# ATtiny_45_and_85_programmer_shield_withI.net
KiCad netlist of a schematic drawn in EAGLE
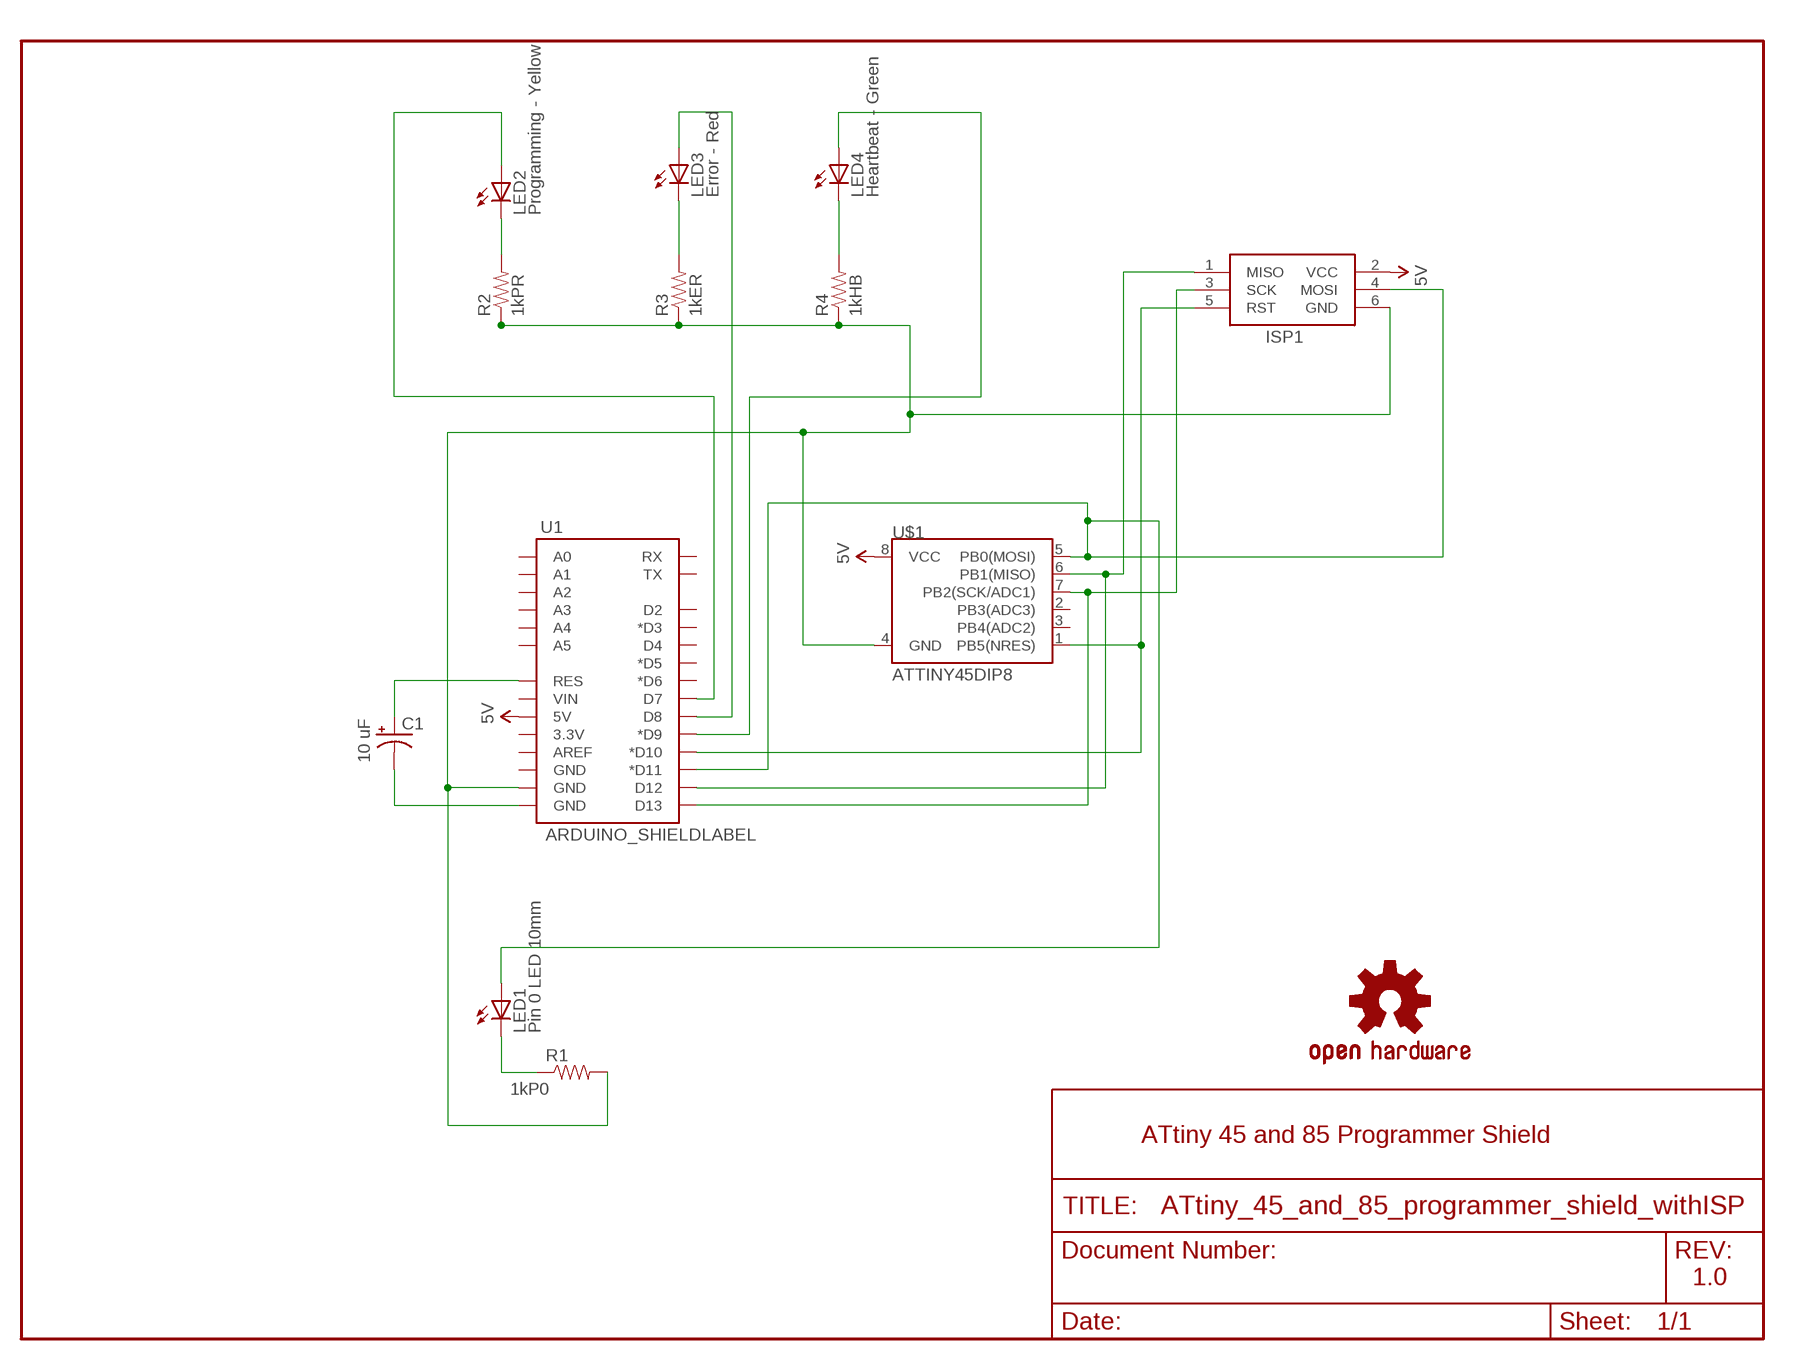
[diagram p0: schematic, sheet 1]

(export (version "E")
  (design (tool "Eeschema 10.0.6"))
  (components
    (comp (ref "C1")
      (value "10 uF")
      (footprint "eagle-import:CPOL-RADIAL-10UF-25V")
      (libsource (lib "eagle-import") (part "CAP_POLPTH2"))
    )
    (comp (ref "ISP1")
      (value "AVRISP-6")
      (footprint "eagle-import:AVRISP")
      (libsource (lib "eagle-import") (part "AVRISP-6"))
    )
    (comp (ref "LED1")
      (value "Pin 0 LED 10mm")
      (footprint "eagle-import:LED10MM")
      (libsource (lib "eagle-import") (part "LED10MM"))
    )
    (comp (ref "LED2")
      (value "Programming - Yellow")
      (footprint "eagle-import:LED5MM")
      (libsource (lib "eagle-import") (part "LED5MM"))
    )
    (comp (ref "LED3")
      (value "Error - Red")
      (footprint "eagle-import:LED5MM")
      (libsource (lib "eagle-import") (part "LED5MM"))
    )
    (comp (ref "LED4")
      (value "Heartbeat - Green")
      (footprint "eagle-import:LED5MM")
      (libsource (lib "eagle-import") (part "LED5MM"))
    )
    (comp (ref "R1")
      (value "1kP0")
      (footprint "eagle-import:1_6W-RES")
      (libsource (lib "eagle-import") (part "RESISTORPTH-1/6W"))
    )
    (comp (ref "R2")
      (value "1kPR")
      (footprint "eagle-import:1_6W-RES")
      (libsource (lib "eagle-import") (part "RESISTORPTH-1/6W"))
    )
    (comp (ref "R3")
      (value "1kER")
      (footprint "eagle-import:1_6W-RES")
      (libsource (lib "eagle-import") (part "RESISTORPTH-1/6W"))
    )
    (comp (ref "R4")
      (value "1kHB")
      (footprint "eagle-import:1_6W-RES")
      (libsource (lib "eagle-import") (part "RESISTORPTH-1/6W"))
    )
    (comp (ref "U$1")
      (value "ATTINY45DIP8")
      (footprint "eagle-import:DIP08")
      (libsource (lib "eagle-import") (part "ATTINY45DIP8"))
    )
    (comp (ref "U$4")
      (value "OSHW-LOGOL")
      (footprint "eagle-import:OSHW-LOGO-L")
      (libsource (lib "eagle-import") (part "OSHW-LOGOL"))
    )
    (comp (ref "U1")
      (value "ARDUINO_SHIELDLABEL")
      (footprint "eagle-import:DUEMILANOVE_SHIELD")
      (libsource (lib "eagle-import") (part "ARDUINO_SHIELDLABEL"))
    )
  )
  (nets
    (net (code "1") (name "5V") (class "Default")
      (node (ref "ISP1") (pin "2") (pinfunction "VCC_2") (pintype "power_in"))
      (node (ref "U$1") (pin "8") (pinfunction "VCC_8") (pintype "bidirectional"))
      (node (ref "U1") (pin "5V") (pinfunction "5V_5V") (pintype "bidirectional"))
    )
    (net (code "2") (name "Net-(C1-+)") (class "Default")
      (node (ref "C1") (pin "1") (pinfunction "+_1") (pintype "passive"))
      (node (ref "U1") (pin "RES") (pinfunction "RES_RES") (pintype "bidirectional"))
    )
    (net (code "3") (name "Net-(C1--)") (class "Default")
      (node (ref "C1") (pin "2") (pinfunction "-_2") (pintype "passive"))
      (node (ref "U1") (pin "GND@0") (pinfunction "GND_GND@0") (pintype "bidirectional"))
    )
    (net (code "4") (name "Net-(ISP1-GND)") (class "Default")
      (node (ref "ISP1") (pin "6") (pinfunction "GND_6") (pintype "power_in"))
      (node (ref "R1") (pin "2") (pinfunction "2_2") (pintype "passive"))
      (node (ref "R2") (pin "1") (pinfunction "1_1") (pintype "passive"))
      (node (ref "R3") (pin "1") (pinfunction "1_1") (pintype "passive"))
      (node (ref "R4") (pin "1") (pinfunction "1_1") (pintype "passive"))
      (node (ref "U$1") (pin "4") (pinfunction "GND_4") (pintype "bidirectional"))
      (node (ref "U1") (pin "GND@1") (pinfunction "GND_GND@1") (pintype "bidirectional"))
    )
    (net (code "5") (name "Net-(ISP1-MISO)") (class "Default")
      (node (ref "ISP1") (pin "1") (pinfunction "MISO_1") (pintype "input"))
      (node (ref "U$1") (pin "6") (pinfunction "PB1(MISO)_6") (pintype "bidirectional"))
      (node (ref "U1") (pin "D12") (pinfunction "D12_D12") (pintype "bidirectional"))
    )
    (net (code "6") (name "Net-(ISP1-MOSI)") (class "Default")
      (node (ref "ISP1") (pin "4") (pinfunction "MOSI_4") (pintype "output"))
      (node (ref "LED1") (pin "A") (pinfunction "A_A") (pintype "passive"))
      (node (ref "U$1") (pin "5") (pinfunction "PB0(MOSI)_5") (pintype "bidirectional"))
      (node (ref "U1") (pin "D11") (pinfunction "*D11_D11") (pintype "bidirectional"))
    )
    (net (code "7") (name "Net-(ISP1-RST)") (class "Default")
      (node (ref "ISP1") (pin "5") (pinfunction "RST_5") (pintype "output"))
      (node (ref "U$1") (pin "1") (pinfunction "PB5(NRES)_1") (pintype "bidirectional"))
      (node (ref "U1") (pin "D10") (pinfunction "*D10_D10") (pintype "bidirectional"))
    )
    (net (code "8") (name "Net-(ISP1-SCK)") (class "Default")
      (node (ref "ISP1") (pin "3") (pinfunction "SCK_3") (pintype "output"))
      (node (ref "U$1") (pin "7") (pinfunction "PB2(SCK/ADC1)_7") (pintype "bidirectional"))
      (node (ref "U1") (pin "D13") (pinfunction "D13_D13") (pintype "bidirectional"))
    )
    (net (code "9") (name "Net-(LED1-PadC)") (class "Default")
      (node (ref "LED1") (pin "C") (pinfunction "C_C") (pintype "passive"))
      (node (ref "R1") (pin "1") (pinfunction "1_1") (pintype "passive"))
    )
    (net (code "10") (name "Net-(LED2-C)") (class "Default")
      (node (ref "LED2") (pin "K") (pinfunction "C_K") (pintype "passive"))
      (node (ref "R2") (pin "2") (pinfunction "2_2") (pintype "passive"))
    )
    (net (code "11") (name "Net-(LED2-PadA)") (class "Default")
      (node (ref "LED2") (pin "A") (pinfunction "A_A") (pintype "passive"))
      (node (ref "U1") (pin "D7") (pinfunction "D7_D7") (pintype "bidirectional"))
    )
    (net (code "12") (name "Net-(LED3-C)") (class "Default")
      (node (ref "LED3") (pin "K") (pinfunction "C_K") (pintype "passive"))
      (node (ref "R3") (pin "2") (pinfunction "2_2") (pintype "passive"))
    )
    (net (code "13") (name "Net-(LED3-PadA)") (class "Default")
      (node (ref "LED3") (pin "A") (pinfunction "A_A") (pintype "passive"))
      (node (ref "U1") (pin "D8") (pinfunction "D8_D8") (pintype "bidirectional"))
    )
    (net (code "14") (name "Net-(LED4-C)") (class "Default")
      (node (ref "LED4") (pin "K") (pinfunction "C_K") (pintype "passive"))
      (node (ref "R4") (pin "2") (pinfunction "2_2") (pintype "passive"))
    )
    (net (code "15") (name "Net-(U1-*D9)") (class "Default")
      (node (ref "LED4") (pin "A") (pinfunction "A_A") (pintype "passive"))
      (node (ref "U1") (pin "D9") (pinfunction "*D9_D9") (pintype "bidirectional"))
    )
    (net (code "16") (name "unconnected-(U$1-PB3(ADC3)-Pad2)") (class "Default")
      (node (ref "U$1") (pin "2") (pinfunction "PB3(ADC3)_2") (pintype "bidirectional"))
    )
    (net (code "17") (name "unconnected-(U$1-PB4(ADC2)-Pad3)") (class "Default")
      (node (ref "U$1") (pin "3") (pinfunction "PB4(ADC2)_3") (pintype "bidirectional"))
    )
    (net (code "18") (name "unconnected-(U1-*D3-PadD3)") (class "Default")
      (node (ref "U1") (pin "D3") (pinfunction "*D3_D3") (pintype "bidirectional"))
    )
    (net (code "19") (name "unconnected-(U1-*D5-PadD5)") (class "Default")
      (node (ref "U1") (pin "D5") (pinfunction "*D5_D5") (pintype "bidirectional"))
    )
    (net (code "20") (name "unconnected-(U1-*D6-PadD6)") (class "Default")
      (node (ref "U1") (pin "D6") (pinfunction "*D6_D6") (pintype "bidirectional"))
    )
    (net (code "21") (name "unconnected-(U1-GND-PadGND@2)") (class "Default")
      (node (ref "U1") (pin "GND@2") (pinfunction "GND_GND@2") (pintype "bidirectional"))
    )
    (net (code "22") (name "unconnected-(U1-Pad3.3V)") (class "Default")
      (node (ref "U1") (pin "3.3V") (pinfunction "3.3V_3.3V") (pintype "bidirectional"))
    )
    (net (code "23") (name "unconnected-(U1-PadA0)") (class "Default")
      (node (ref "U1") (pin "A0") (pinfunction "A0_A0") (pintype "bidirectional"))
    )
    (net (code "24") (name "unconnected-(U1-PadA1)") (class "Default")
      (node (ref "U1") (pin "A1") (pinfunction "A1_A1") (pintype "bidirectional"))
    )
    (net (code "25") (name "unconnected-(U1-PadA2)") (class "Default")
      (node (ref "U1") (pin "A2") (pinfunction "A2_A2") (pintype "bidirectional"))
    )
    (net (code "26") (name "unconnected-(U1-PadA3)") (class "Default")
      (node (ref "U1") (pin "A3") (pinfunction "A3_A3") (pintype "bidirectional"))
    )
    (net (code "27") (name "unconnected-(U1-PadA4)") (class "Default")
      (node (ref "U1") (pin "A4") (pinfunction "A4_A4") (pintype "bidirectional"))
    )
    (net (code "28") (name "unconnected-(U1-PadA5)") (class "Default")
      (node (ref "U1") (pin "A5") (pinfunction "A5_A5") (pintype "bidirectional"))
    )
    (net (code "29") (name "unconnected-(U1-PadAREF)") (class "Default")
      (node (ref "U1") (pin "AREF") (pinfunction "AREF_AREF") (pintype "bidirectional"))
    )
    (net (code "30") (name "unconnected-(U1-PadD2)") (class "Default")
      (node (ref "U1") (pin "D2") (pinfunction "D2_D2") (pintype "bidirectional"))
    )
    (net (code "31") (name "unconnected-(U1-PadD4)") (class "Default")
      (node (ref "U1") (pin "D4") (pinfunction "D4_D4") (pintype "bidirectional"))
    )
    (net (code "32") (name "unconnected-(U1-PadRX)") (class "Default")
      (node (ref "U1") (pin "RX") (pinfunction "RX_RX") (pintype "bidirectional"))
    )
    (net (code "33") (name "unconnected-(U1-PadTX)") (class "Default")
      (node (ref "U1") (pin "TX") (pinfunction "TX_TX") (pintype "bidirectional"))
    )
    (net (code "34") (name "unconnected-(U1-PadVIN)") (class "Default")
      (node (ref "U1") (pin "VIN") (pinfunction "VIN_VIN") (pintype "bidirectional"))
    )
  )
)
